# LTC3105_Breakout.net
KiCad netlist of a schematic drawn in EAGLE
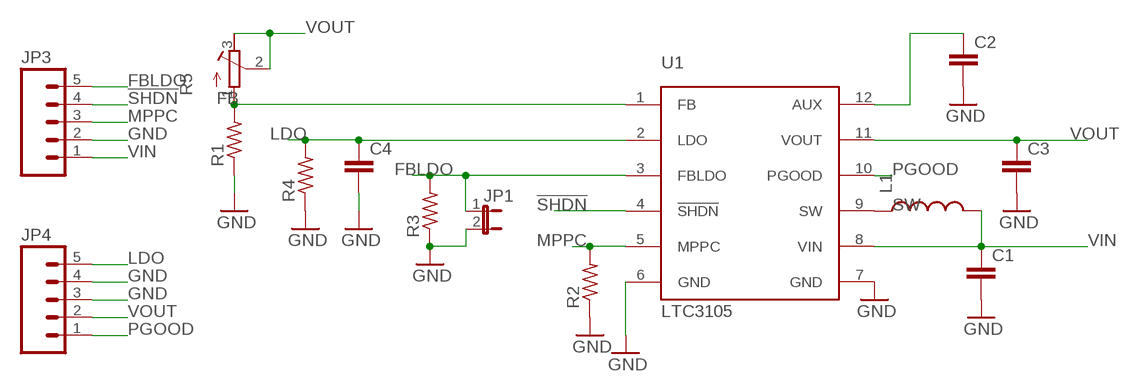
[diagram p0: schematic, sheet 1]

(export (version "E")
  (design (tool "Eeschema 10.0.6"))
  (components
    (comp (ref "C1")
      (value "C-EUC0805")
      (footprint "eagle-import:C0805")
      (libsource (lib "eagle-import") (part "C-EUC0805"))
    )
    (comp (ref "C2")
      (value "C-EUC0603")
      (footprint "eagle-import:C0603")
      (libsource (lib "eagle-import") (part "C-EUC0603"))
    )
    (comp (ref "C3")
      (value "C-EUC0805")
      (footprint "eagle-import:C0805")
      (libsource (lib "eagle-import") (part "C-EUC0805"))
    )
    (comp (ref "C4")
      (value "C-EUC0805")
      (footprint "eagle-import:C0805")
      (libsource (lib "eagle-import") (part "C-EUC0805"))
    )
    (comp (ref "JP1")
      (value "JUMPER-2SMD-NO")
      (footprint "eagle-import:SJ_2S-NO")
      (libsource (lib "eagle-import") (part "JUMPER-2SMD-NO"))
    )
    (comp (ref "JP3")
      (value "M05PTH")
      (footprint "eagle-import:1X05")
      (libsource (lib "eagle-import") (part "M05PTH"))
    )
    (comp (ref "JP4")
      (value "M05PTH")
      (footprint "eagle-import:1X05")
      (libsource (lib "eagle-import") (part "M05PTH"))
    )
    (comp (ref "L1")
      (value "INDUCTOR1210")
      (footprint "eagle-import:1210")
      (libsource (lib "eagle-import") (part "INDUCTOR1210"))
    )
    (comp (ref "R1")
      (value "R-US_R0603")
      (footprint "eagle-import:R0603")
      (libsource (lib "eagle-import") (part "R-US_R0603"))
    )
    (comp (ref "R2")
      (value "R-US_R0603")
      (footprint "eagle-import:R0603")
      (libsource (lib "eagle-import") (part "R-US_R0603"))
    )
    (comp (ref "R3")
      (value "R-US_R0603")
      (footprint "eagle-import:R0603")
      (libsource (lib "eagle-import") (part "R-US_R0603"))
    )
    (comp (ref "R4")
      (value "R-US_R0603")
      (footprint "eagle-import:R0603")
      (libsource (lib "eagle-import") (part "R-US_R0603"))
    )
    (comp (ref "R5")
      (value "R-TRIMM3314J")
      (footprint "eagle-import:RTRIM3314J")
      (libsource (lib "eagle-import") (part "R-TRIMM3314J"))
    )
    (comp (ref "U1")
      (value "LTC3105")
      (footprint "eagle-import:MSOP")
      (libsource (lib "eagle-import") (part "LTC3105"))
    )
  )
  (nets
    (net (code "1") (name "/FB") (class "Default")
      (node (ref "R1") (pin "2") (pinfunction "2_2") (pintype "passive"))
      (node (ref "R5") (pin "1") (pinfunction "E_1") (pintype "passive"))
      (node (ref "U1") (pin "1") (pinfunction "FB_1") (pintype "bidirectional"))
    )
    (net (code "2") (name "/FBLDO") (class "Default")
      (node (ref "JP1") (pin "1") (pinfunction "1_1") (pintype "passive"))
      (node (ref "JP3") (pin "5") (pinfunction "5_5") (pintype "passive"))
      (node (ref "R3") (pin "2") (pinfunction "2_2") (pintype "passive"))
      (node (ref "U1") (pin "3") (pinfunction "FBLDO_3") (pintype "bidirectional"))
    )
    (net (code "3") (name "/LDO") (class "Default")
      (node (ref "C4") (pin "1") (pinfunction "1_1") (pintype "passive"))
      (node (ref "JP4") (pin "5") (pinfunction "5_5") (pintype "passive"))
      (node (ref "R4") (pin "2") (pinfunction "2_2") (pintype "passive"))
      (node (ref "U1") (pin "2") (pinfunction "LDO_2") (pintype "bidirectional"))
    )
    (net (code "4") (name "/MPPC") (class "Default")
      (node (ref "JP3") (pin "3") (pinfunction "3_3") (pintype "passive"))
      (node (ref "R2") (pin "2") (pinfunction "2_2") (pintype "passive"))
      (node (ref "U1") (pin "5") (pinfunction "MPPC_5") (pintype "bidirectional"))
    )
    (net (code "5") (name "/PGOOD") (class "Default")
      (node (ref "JP4") (pin "1") (pinfunction "1_1") (pintype "passive"))
      (node (ref "U1") (pin "10") (pinfunction "PGOOD_10") (pintype "bidirectional"))
    )
    (net (code "7") (name "/VIN") (class "Default")
      (node (ref "C1") (pin "1") (pinfunction "1_1") (pintype "passive"))
      (node (ref "JP3") (pin "1") (pinfunction "1_1") (pintype "passive"))
      (node (ref "L1") (pin "2") (pinfunction "2_2") (pintype "passive"))
      (node (ref "U1") (pin "8") (pinfunction "VIN_8") (pintype "bidirectional"))
    )
    (net (code "8") (name "/VOUT") (class "Default")
      (node (ref "C3") (pin "1") (pinfunction "1_1") (pintype "passive"))
      (node (ref "JP4") (pin "2") (pinfunction "2_2") (pintype "passive"))
      (node (ref "R5") (pin "2") (pinfunction "S_2") (pintype "passive"))
      (node (ref "R5") (pin "3") (pinfunction "A_3") (pintype "passive"))
      (node (ref "U1") (pin "11") (pinfunction "VOUT_11") (pintype "bidirectional"))
    )
    (net (code "9") (name "/~{SHDN}") (class "Default")
      (node (ref "JP3") (pin "4") (pinfunction "4_4") (pintype "passive"))
      (node (ref "U1") (pin "4") (pinfunction "~{SHDN}_4") (pintype "bidirectional"))
    )
    (net (code "10") (name "GND") (class "Default")
      (node (ref "C1") (pin "2") (pinfunction "2_2") (pintype "passive"))
      (node (ref "C2") (pin "2") (pinfunction "2_2") (pintype "passive"))
      (node (ref "C3") (pin "2") (pinfunction "2_2") (pintype "passive"))
      (node (ref "C4") (pin "2") (pinfunction "2_2") (pintype "passive"))
      (node (ref "JP1") (pin "2") (pinfunction "2_2") (pintype "passive"))
      (node (ref "JP3") (pin "2") (pinfunction "2_2") (pintype "passive"))
      (node (ref "JP4") (pin "3") (pinfunction "3_3") (pintype "passive"))
      (node (ref "JP4") (pin "4") (pinfunction "4_4") (pintype "passive"))
      (node (ref "R1") (pin "1") (pinfunction "1_1") (pintype "passive"))
      (node (ref "R2") (pin "1") (pinfunction "1_1") (pintype "passive"))
      (node (ref "R3") (pin "1") (pinfunction "1_1") (pintype "passive"))
      (node (ref "R4") (pin "1") (pinfunction "1_1") (pintype "passive"))
      (node (ref "U1") (pin "6") (pinfunction "GND_6") (pintype "bidirectional"))
      (node (ref "U1") (pin "7") (pinfunction "GND_7") (pintype "bidirectional"))
    )
    (net (code "11") (name "Net-(U1-AUX)") (class "Default")
      (node (ref "C2") (pin "1") (pinfunction "1_1") (pintype "passive"))
      (node (ref "U1") (pin "12") (pinfunction "AUX_12") (pintype "bidirectional"))
    )
    (net (code "12") (name "Net-(U1-SW)") (class "Default")
      (node (ref "L1") (pin "1") (pinfunction "1_1") (pintype "passive"))
      (node (ref "U1") (pin "9") (pinfunction "SW_9") (pintype "bidirectional"))
    )
  )
)
